# odrb_redraw.net
KiCad netlist of a schematic drawn in EAGLE
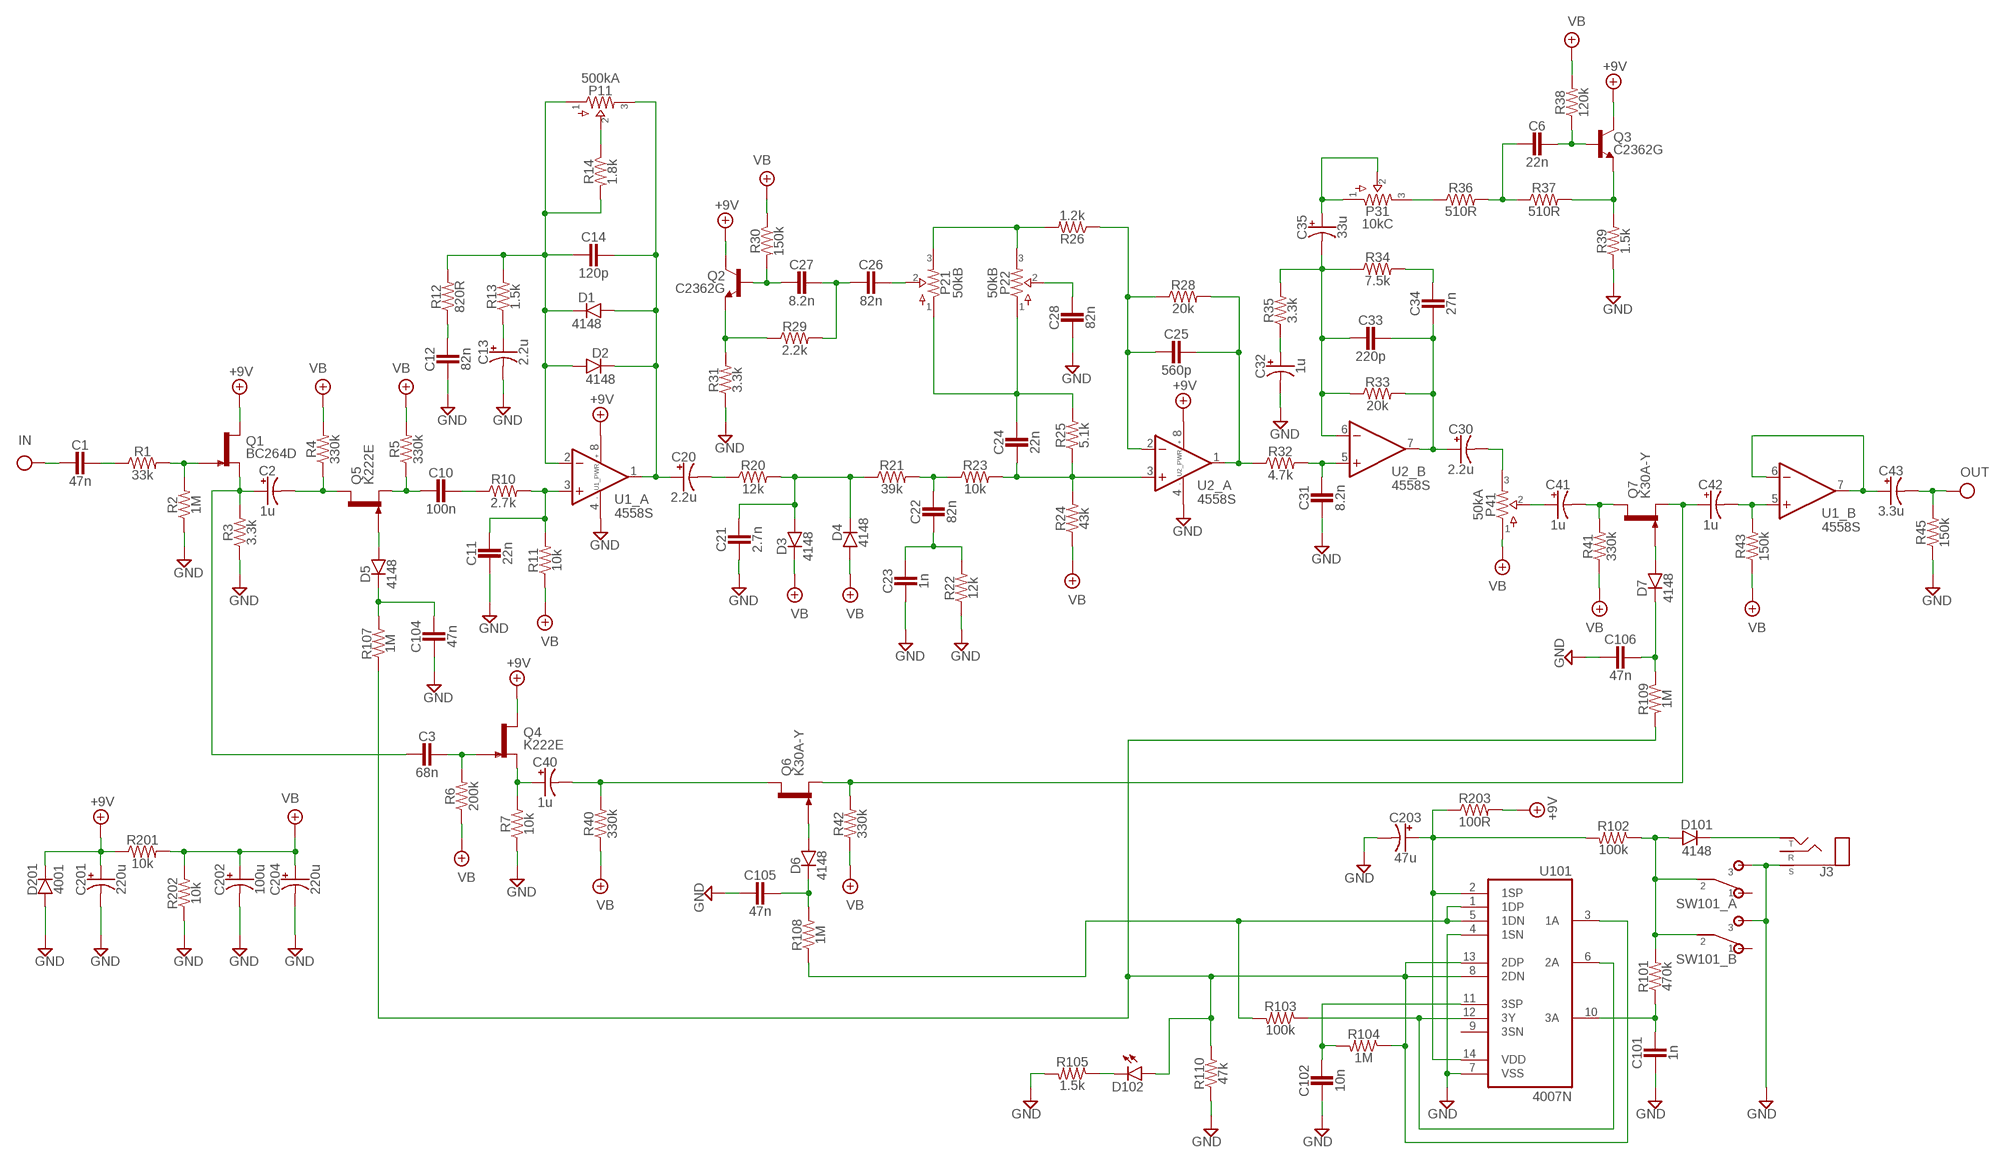
[diagram p0: schematic, sheet 1]

(export (version "E")
  (design (tool "Eeschema 10.0.6"))
  (components
    (comp (ref "C1")
      (value "47n")
      (footprint "eagle-import:BOX_SMALL")
      (libsource (lib "eagle-import") (part "CER/FILMBOX.1"))
    )
    (comp (ref "C2")
      (value "1u")
      (footprint "eagle-import:050_020")
      (libsource (lib "eagle-import") (part "0500"))
    )
    (comp (ref "C3")
      (value "68n")
      (footprint "eagle-import:BOX_SMALL")
      (libsource (lib "eagle-import") (part "CER/FILMBOX.1"))
    )
    (comp (ref "C6")
      (value "22n")
      (footprint "eagle-import:BOX_SMALL")
      (libsource (lib "eagle-import") (part "CER/FILMBOX.1"))
    )
    (comp (ref "C10")
      (value "100n")
      (footprint "eagle-import:BOX_SMALL")
      (libsource (lib "eagle-import") (part "CER/FILMBOX.1"))
    )
    (comp (ref "C11")
      (value "22n")
      (footprint "eagle-import:BOX_SMALL")
      (libsource (lib "eagle-import") (part "CER/FILMBOX.1"))
    )
    (comp (ref "C12")
      (value "82n")
      (footprint "eagle-import:BOX_SMALL")
      (libsource (lib "eagle-import") (part "CER/FILMBOX.1"))
    )
    (comp (ref "C13")
      (value "2.2u")
      (footprint "eagle-import:040_020")
      (libsource (lib "eagle-import") (part "0400"))
    )
    (comp (ref "C14")
      (value "120p")
      (footprint "eagle-import:BOX_SMALL")
      (libsource (lib "eagle-import") (part "CER/FILMBOX.1"))
    )
    (comp (ref "C20")
      (value "2.2u")
      (footprint "eagle-import:040_020")
      (libsource (lib "eagle-import") (part "0400"))
    )
    (comp (ref "C21")
      (value "2.7n")
      (footprint "eagle-import:BOX_SMALL")
      (libsource (lib "eagle-import") (part "CER/FILMBOX.1"))
    )
    (comp (ref "C22")
      (value "82n")
      (footprint "eagle-import:BOX_SMALL")
      (libsource (lib "eagle-import") (part "CER/FILMBOX.1"))
    )
    (comp (ref "C23")
      (value "1n")
      (footprint "eagle-import:BOX_SMALL")
      (libsource (lib "eagle-import") (part "CER/FILMBOX.1"))
    )
    (comp (ref "C24")
      (value "22n")
      (footprint "eagle-import:BOX_SMALL")
      (libsource (lib "eagle-import") (part "CER/FILMBOX.1"))
    )
    (comp (ref "C25")
      (value "560p")
      (footprint "eagle-import:BOX_SMALL")
      (libsource (lib "eagle-import") (part "CER/FILMBOX.1"))
    )
    (comp (ref "C26")
      (value "82n")
      (footprint "eagle-import:BOX_SMALL")
      (libsource (lib "eagle-import") (part "CER/FILMBOX.1"))
    )
    (comp (ref "C27")
      (value "8.2n")
      (footprint "eagle-import:BOX_SMALL")
      (libsource (lib "eagle-import") (part "CER/FILMBOX.1"))
    )
    (comp (ref "C28")
      (value "82n")
      (footprint "eagle-import:BOX_SMALL")
      (libsource (lib "eagle-import") (part "CER/FILMBOX.1"))
    )
    (comp (ref "C30")
      (value "2.2u")
      (footprint "eagle-import:040_020")
      (libsource (lib "eagle-import") (part "0400"))
    )
    (comp (ref "C31")
      (value "8.2n")
      (footprint "eagle-import:BOX_SMALL")
      (libsource (lib "eagle-import") (part "CER/FILMBOX.1"))
    )
    (comp (ref "C32")
      (value "1u")
      (footprint "eagle-import:040_020")
      (libsource (lib "eagle-import") (part "0400"))
    )
    (comp (ref "C33")
      (value "220p")
      (footprint "eagle-import:BOX_SMALL")
      (libsource (lib "eagle-import") (part "CER/FILMBOX.1"))
    )
    (comp (ref "C34")
      (value "27n")
      (footprint "eagle-import:BOX_SMALL")
      (libsource (lib "eagle-import") (part "CER/FILMBOX.1"))
    )
    (comp (ref "C35")
      (value "33u")
      (footprint "eagle-import:040_020")
      (libsource (lib "eagle-import") (part "0400"))
    )
    (comp (ref "C40")
      (value "1u")
      (footprint "eagle-import:040_020")
      (libsource (lib "eagle-import") (part "0400"))
    )
    (comp (ref "C41")
      (value "1u")
      (footprint "eagle-import:040_020")
      (libsource (lib "eagle-import") (part "0400"))
    )
    (comp (ref "C42")
      (value "1u")
      (footprint "eagle-import:040_020")
      (libsource (lib "eagle-import") (part "0400"))
    )
    (comp (ref "C43")
      (value "3.3u")
      (footprint "eagle-import:040_020")
      (libsource (lib "eagle-import") (part "0400"))
    )
    (comp (ref "C101")
      (value "1n")
      (footprint "eagle-import:BOX_SMALL")
      (libsource (lib "eagle-import") (part "CER/FILMBOX.1"))
    )
    (comp (ref "C102")
      (value "10n")
      (footprint "eagle-import:BOX_SMALL")
      (libsource (lib "eagle-import") (part "CER/FILMBOX.1"))
    )
    (comp (ref "C104")
      (value "47n")
      (footprint "eagle-import:BOX_SMALL")
      (libsource (lib "eagle-import") (part "CER/FILMBOX.1"))
    )
    (comp (ref "C105")
      (value "47n")
      (footprint "eagle-import:BOX_SMALL")
      (libsource (lib "eagle-import") (part "CER/FILMBOX.1"))
    )
    (comp (ref "C106")
      (value "47n")
      (footprint "eagle-import:BOX_SMALL")
      (libsource (lib "eagle-import") (part "CER/FILMBOX.1"))
    )
    (comp (ref "C201")
      (value "220u")
      (footprint "eagle-import:040_020")
      (libsource (lib "eagle-import") (part "0400"))
    )
    (comp (ref "C202")
      (value "100u")
      (footprint "eagle-import:040_020")
      (libsource (lib "eagle-import") (part "0400"))
    )
    (comp (ref "C203")
      (value "47u")
      (footprint "eagle-import:040_020")
      (libsource (lib "eagle-import") (part "0400"))
    )
    (comp (ref "C204")
      (value "220u")
      (footprint "eagle-import:040_020")
      (libsource (lib "eagle-import") (part "0400"))
    )
    (comp (ref "D1")
      (value "4148")
      (footprint "eagle-import:DO35-2")
      (libsource (lib "eagle-import") (part "DO35.2"))
    )
    (comp (ref "D2")
      (value "4148")
      (footprint "eagle-import:DO35-2")
      (libsource (lib "eagle-import") (part "DO35.2"))
    )
    (comp (ref "D3")
      (value "4148")
      (footprint "eagle-import:DO35-2")
      (libsource (lib "eagle-import") (part "DO35.2"))
    )
    (comp (ref "D4")
      (value "4148")
      (footprint "eagle-import:DO35-2")
      (libsource (lib "eagle-import") (part "DO35.2"))
    )
    (comp (ref "D5")
      (value "4148")
      (footprint "eagle-import:DO35-2")
      (libsource (lib "eagle-import") (part "DO35.2"))
    )
    (comp (ref "D6")
      (value "4148")
      (footprint "eagle-import:DO35-2")
      (libsource (lib "eagle-import") (part "DO35.2"))
    )
    (comp (ref "D7")
      (value "4148")
      (footprint "eagle-import:DO35-2")
      (libsource (lib "eagle-import") (part "DO35.2"))
    )
    (comp (ref "D101")
      (value "4148")
      (footprint "eagle-import:DO35-2")
      (libsource (lib "eagle-import") (part "DO35.2"))
    )
    (comp (ref "D102")
      (value "LED")
      (footprint "eagle-import:3MM_D")
      (libsource (lib "eagle-import") (part "LED"))
    )
    (comp (ref "D201")
      (value "4001")
      (footprint "eagle-import:DO35-2")
      (libsource (lib "eagle-import") (part "DO35.2"))
    )
    (comp (ref "J3")
      (value "STEREO3PADS")
      (footprint "eagle-import:THREEPADS")
      (libsource (lib "eagle-import") (part "STEREO3PADS"))
    )
    (comp (ref "P11")
      (value "500kA")
      (footprint "eagle-import:16MM")
      (libsource (lib "eagle-import") (part "POTS16MM"))
    )
    (comp (ref "P21")
      (value "50kB")
      (footprint "eagle-import:16MM")
      (libsource (lib "eagle-import") (part "POTS16MM"))
    )
    (comp (ref "P22")
      (value "50kB")
      (footprint "eagle-import:16MM")
      (libsource (lib "eagle-import") (part "POTS16MM"))
    )
    (comp (ref "P31")
      (value "10kC")
      (footprint "eagle-import:16MM")
      (libsource (lib "eagle-import") (part "POTS16MM"))
    )
    (comp (ref "P41")
      (value "50kA")
      (footprint "eagle-import:16MM")
      (libsource (lib "eagle-import") (part "POTS16MM"))
    )
    (comp (ref "Q1")
      (value "BC264D")
      (footprint "eagle-import:TO92-")
      (libsource (lib "eagle-import") (part "2N3819TO-92S"))
    )
    (comp (ref "Q2")
      (value "C2362G")
      (footprint "eagle-import:TO92-")
      (libsource (lib "eagle-import") (part "2N3904"))
    )
    (comp (ref "Q3")
      (value "C2362G")
      (footprint "eagle-import:TO92-")
      (libsource (lib "eagle-import") (part "2N3904"))
    )
    (comp (ref "Q4")
      (value "K222E")
      (footprint "eagle-import:TO92-")
      (libsource (lib "eagle-import") (part "2N3819TO-92S"))
    )
    (comp (ref "Q5")
      (value "K222E")
      (footprint "eagle-import:TO92-")
      (libsource (lib "eagle-import") (part "2N3819TO-92S"))
    )
    (comp (ref "Q6")
      (value "K30A-Y")
      (footprint "eagle-import:TO92-")
      (libsource (lib "eagle-import") (part "2N3819TO-92S"))
    )
    (comp (ref "Q7")
      (value "K30A-Y")
      (footprint "eagle-import:TO92-")
      (libsource (lib "eagle-import") (part "2N3819TO-92S"))
    )
    (comp (ref "R1")
      (value "33k")
      (footprint "eagle-import:R0207_3")
      (libsource (lib "eagle-import") (part "R_.3B"))
    )
    (comp (ref "R2")
      (value "1M")
      (footprint "eagle-import:R0207_3")
      (libsource (lib "eagle-import") (part "R_.3B"))
    )
    (comp (ref "R3")
      (value "3.3k")
      (footprint "eagle-import:R0207_3")
      (libsource (lib "eagle-import") (part "R_.3B"))
    )
    (comp (ref "R4")
      (value "330k")
      (footprint "eagle-import:R0207_3")
      (libsource (lib "eagle-import") (part "R_.3B"))
    )
    (comp (ref "R5")
      (value "330k")
      (footprint "eagle-import:R0207_3")
      (libsource (lib "eagle-import") (part "R_.3B"))
    )
    (comp (ref "R6")
      (value "200k")
      (footprint "eagle-import:R0207_3")
      (libsource (lib "eagle-import") (part "R_.3B"))
    )
    (comp (ref "R7")
      (value "10k")
      (footprint "eagle-import:R0207_3")
      (libsource (lib "eagle-import") (part "R_.3B"))
    )
    (comp (ref "R10")
      (value "2.7k")
      (footprint "eagle-import:R0207_3")
      (libsource (lib "eagle-import") (part "R_.3B"))
    )
    (comp (ref "R11")
      (value "10k")
      (footprint "eagle-import:R0207_3")
      (libsource (lib "eagle-import") (part "R_.3B"))
    )
    (comp (ref "R12")
      (value "820R")
      (footprint "eagle-import:R0207_3")
      (libsource (lib "eagle-import") (part "R_.3B"))
    )
    (comp (ref "R13")
      (value "1.5k")
      (footprint "eagle-import:R0207_3")
      (libsource (lib "eagle-import") (part "R_.3B"))
    )
    (comp (ref "R14")
      (value "1.8k")
      (footprint "eagle-import:R0207_3")
      (libsource (lib "eagle-import") (part "R_.3B"))
    )
    (comp (ref "R20")
      (value "12k")
      (footprint "eagle-import:R0207_3")
      (libsource (lib "eagle-import") (part "R_.3B"))
    )
    (comp (ref "R21")
      (value "39k")
      (footprint "eagle-import:R0207_3")
      (libsource (lib "eagle-import") (part "R_.3B"))
    )
    (comp (ref "R22")
      (value "12k")
      (footprint "eagle-import:R0207_3")
      (libsource (lib "eagle-import") (part "R_.3B"))
    )
    (comp (ref "R23")
      (value "10k")
      (footprint "eagle-import:R0207_3")
      (libsource (lib "eagle-import") (part "R_.3B"))
    )
    (comp (ref "R24")
      (value "43k")
      (footprint "eagle-import:R0207_3")
      (libsource (lib "eagle-import") (part "R_.3B"))
    )
    (comp (ref "R25")
      (value "5.1k")
      (footprint "eagle-import:R0207_3")
      (libsource (lib "eagle-import") (part "R_.3B"))
    )
    (comp (ref "R26")
      (value "1.2k")
      (footprint "eagle-import:R0207_3")
      (libsource (lib "eagle-import") (part "R_.3B"))
    )
    (comp (ref "R28")
      (value "20k")
      (footprint "eagle-import:R0207_3")
      (libsource (lib "eagle-import") (part "R_.3B"))
    )
    (comp (ref "R29")
      (value "2.2k")
      (footprint "eagle-import:R0207_3")
      (libsource (lib "eagle-import") (part "R_.3B"))
    )
    (comp (ref "R30")
      (value "150k")
      (footprint "eagle-import:R0207_3")
      (libsource (lib "eagle-import") (part "R_.3B"))
    )
    (comp (ref "R31")
      (value "3.3k")
      (footprint "eagle-import:R0207_3")
      (libsource (lib "eagle-import") (part "R_.3B"))
    )
    (comp (ref "R32")
      (value "4.7k")
      (footprint "eagle-import:R0207_3")
      (libsource (lib "eagle-import") (part "R_.3B"))
    )
    (comp (ref "R33")
      (value "20k")
      (footprint "eagle-import:R0207_3")
      (libsource (lib "eagle-import") (part "R_.3B"))
    )
    (comp (ref "R34")
      (value "7.5k")
      (footprint "eagle-import:R0207_3")
      (libsource (lib "eagle-import") (part "R_.3B"))
    )
    (comp (ref "R35")
      (value "3.3k")
      (footprint "eagle-import:R0207_3")
      (libsource (lib "eagle-import") (part "R_.3B"))
    )
    (comp (ref "R36")
      (value "510R")
      (footprint "eagle-import:R0207_3")
      (libsource (lib "eagle-import") (part "R_.3B"))
    )
    (comp (ref "R37")
      (value "510R")
      (footprint "eagle-import:R0207_3")
      (libsource (lib "eagle-import") (part "R_.3B"))
    )
    (comp (ref "R38")
      (value "120k")
      (footprint "eagle-import:R0207_3")
      (libsource (lib "eagle-import") (part "R_.3B"))
    )
    (comp (ref "R39")
      (value "1.5k")
      (footprint "eagle-import:R0207_3")
      (libsource (lib "eagle-import") (part "R_.3B"))
    )
    (comp (ref "R40")
      (value "330k")
      (footprint "eagle-import:R0207_3")
      (libsource (lib "eagle-import") (part "R_.3B"))
    )
    (comp (ref "R41")
      (value "330k")
      (footprint "eagle-import:R0207_3")
      (libsource (lib "eagle-import") (part "R_.3B"))
    )
    (comp (ref "R42")
      (value "330k")
      (footprint "eagle-import:R0207_3")
      (libsource (lib "eagle-import") (part "R_.3B"))
    )
    (comp (ref "R43")
      (value "150k")
      (footprint "eagle-import:R0207_3")
      (libsource (lib "eagle-import") (part "R_.3B"))
    )
    (comp (ref "R45")
      (value "150k")
      (footprint "eagle-import:R0207_3")
      (libsource (lib "eagle-import") (part "R_.3B"))
    )
    (comp (ref "R101")
      (value "470k")
      (footprint "eagle-import:R0207_3")
      (libsource (lib "eagle-import") (part "R_.3B"))
    )
    (comp (ref "R102")
      (value "100k")
      (footprint "eagle-import:R0207_3")
      (libsource (lib "eagle-import") (part "R_.3B"))
    )
    (comp (ref "R103")
      (value "100k")
      (footprint "eagle-import:R0207_3")
      (libsource (lib "eagle-import") (part "R_.3B"))
    )
    (comp (ref "R104")
      (value "1M")
      (footprint "eagle-import:R0207_3")
      (libsource (lib "eagle-import") (part "R_.3B"))
    )
    (comp (ref "R105")
      (value "1.5k")
      (footprint "eagle-import:R0207_3")
      (libsource (lib "eagle-import") (part "R_.3B"))
    )
    (comp (ref "R107")
      (value "1M")
      (footprint "eagle-import:R0207_3")
      (libsource (lib "eagle-import") (part "R_.3B"))
    )
    (comp (ref "R108")
      (value "1M")
      (footprint "eagle-import:R0207_3")
      (libsource (lib "eagle-import") (part "R_.3B"))
    )
    (comp (ref "R109")
      (value "1M")
      (footprint "eagle-import:R0207_3")
      (libsource (lib "eagle-import") (part "R_.3B"))
    )
    (comp (ref "R110")
      (value "47k")
      (footprint "eagle-import:R0207_3")
      (libsource (lib "eagle-import") (part "R_.3B"))
    )
    (comp (ref "R201")
      (value "10k")
      (footprint "eagle-import:R0207_3")
      (libsource (lib "eagle-import") (part "R_.3B"))
    )
    (comp (ref "R202")
      (value "10k")
      (footprint "eagle-import:R0207_3")
      (libsource (lib "eagle-import") (part "R_.3B"))
    )
    (comp (ref "R203")
      (value "100R")
      (footprint "eagle-import:R0207_3")
      (libsource (lib "eagle-import") (part "R_.3B"))
    )
    (comp (ref "SW101")
      (value "DPDT")
      (footprint "eagle-import:DPDT")
      (libsource (lib "eagle-import") (part "DPDT"))
    )
    (comp (ref "U1")
      (value "4558S")
      (footprint "eagle-import:DIL0")
      (libsource (lib "eagle-import") (part "DUALTH"))
    )
    (comp (ref "U2")
      (value "4558S")
      (footprint "eagle-import:DIL0")
      (libsource (lib "eagle-import") (part "DUALTH"))
    )
    (comp (ref "U101")
      (value "4007N")
      (footprint "eagle-import:DIL14")
      (libsource (lib "eagle-import") (part "4007N"))
    )
  )
  (nets
    (net (code "1") (name "+9V") (class "Default")
      (node (ref "C201") (pin "+") (pinfunction "+_+") (pintype "passive"))
      (node (ref "D201") (pin "C") (pinfunction "C_C") (pintype "passive"))
      (node (ref "Q1") (pin "3") (pinfunction "D_3") (pintype "passive"))
      (node (ref "Q2") (pin "1") (pinfunction "C_1") (pintype "passive"))
      (node (ref "Q3") (pin "1") (pinfunction "C_1") (pintype "passive"))
      (node (ref "Q4") (pin "3") (pinfunction "D_3") (pintype "passive"))
      (node (ref "R201") (pin "1") (pinfunction "1_1") (pintype "passive"))
      (node (ref "R203") (pin "2") (pinfunction "2_2") (pintype "passive"))
      (node (ref "U1") (pin "8") (pinfunction "V+_8") (pintype "power_in"))
      (node (ref "U2") (pin "8") (pinfunction "V+_8") (pintype "power_in"))
    )
    (net (code "2") (name "GND") (class "Default")
      (node (ref "C101") (pin "2") (pinfunction "2_2") (pintype "passive"))
      (node (ref "C102") (pin "2") (pinfunction "2_2") (pintype "passive"))
      (node (ref "C104") (pin "1") (pinfunction "1_1") (pintype "passive"))
      (node (ref "C105") (pin "2") (pinfunction "2_2") (pintype "passive"))
      (node (ref "C106") (pin "2") (pinfunction "2_2") (pintype "passive"))
      (node (ref "C11") (pin "2") (pinfunction "2_2") (pintype "passive"))
      (node (ref "C12") (pin "2") (pinfunction "2_2") (pintype "passive"))
      (node (ref "C13") (pin "-") (pinfunction "-_-") (pintype "passive"))
      (node (ref "C201") (pin "-") (pinfunction "-_-") (pintype "passive"))
      (node (ref "C202") (pin "-") (pinfunction "-_-") (pintype "passive"))
      (node (ref "C203") (pin "-") (pinfunction "-_-") (pintype "passive"))
      (node (ref "C204") (pin "-") (pinfunction "-_-") (pintype "passive"))
      (node (ref "C21") (pin "2") (pinfunction "2_2") (pintype "passive"))
      (node (ref "C23") (pin "2") (pinfunction "2_2") (pintype "passive"))
      (node (ref "C28") (pin "2") (pinfunction "2_2") (pintype "passive"))
      (node (ref "C31") (pin "2") (pinfunction "2_2") (pintype "passive"))
      (node (ref "C32") (pin "-") (pinfunction "-_-") (pintype "passive"))
      (node (ref "D201") (pin "A") (pinfunction "A_A") (pintype "passive"))
      (node (ref "J3") (pin "SLEEVE") (pinfunction "S_SLEEVE") (pintype "passive"))
      (node (ref "R105") (pin "2") (pinfunction "2_2") (pintype "passive"))
      (node (ref "R110") (pin "1") (pinfunction "1_1") (pintype "passive"))
      (node (ref "R2") (pin "1") (pinfunction "1_1") (pintype "passive"))
      (node (ref "R202") (pin "1") (pinfunction "1_1") (pintype "passive"))
      (node (ref "R22") (pin "1") (pinfunction "1_1") (pintype "passive"))
      (node (ref "R3") (pin "1") (pinfunction "1_1") (pintype "passive"))
      (node (ref "R31") (pin "1") (pinfunction "1_1") (pintype "passive"))
      (node (ref "R39") (pin "1") (pinfunction "1_1") (pintype "passive"))
      (node (ref "R45") (pin "1") (pinfunction "1_1") (pintype "passive"))
      (node (ref "R7") (pin "1") (pinfunction "1_1") (pintype "passive"))
      (node (ref "SW101") (pin "A3") (pinfunction "3_A3") (pintype "passive"))
      (node (ref "SW101") (pin "B3") (pinfunction "3_B3") (pintype "passive"))
      (node (ref "U1") (pin "4") (pinfunction "V-_4") (pintype "power_in"))
      (node (ref "U101") (pin "4") (pinfunction "1SN_4") (pintype "open_collector"))
      (node (ref "U101") (pin "7") (pinfunction "VSS_7") (pintype "input"))
      (node (ref "U2") (pin "4") (pinfunction "V-_4") (pintype "power_in"))
    )
    (net (code "3") (name "IN") (class "Default")
      (node (ref "C1") (pin "2") (pinfunction "2_2") (pintype "passive"))
    )
    (net (code "4") (name "Net-(C1-Pad1)") (class "Default")
      (node (ref "C1") (pin "1") (pinfunction "1_1") (pintype "passive"))
      (node (ref "R1") (pin "1") (pinfunction "1_1") (pintype "passive"))
    )
    (net (code "5") (name "Net-(C6-Pad2)") (class "Default")
      (node (ref "C6") (pin "2") (pinfunction "2_2") (pintype "passive"))
      (node (ref "R36") (pin "2") (pinfunction "2_2") (pintype "passive"))
      (node (ref "R37") (pin "1") (pinfunction "1_1") (pintype "passive"))
    )
    (net (code "6") (name "Net-(C10-Pad1)") (class "Default")
      (node (ref "C10") (pin "1") (pinfunction "1_1") (pintype "passive"))
      (node (ref "R10") (pin "1") (pinfunction "1_1") (pintype "passive"))
    )
    (net (code "7") (name "Net-(C12-Pad1)") (class "Default")
      (node (ref "C12") (pin "1") (pinfunction "1_1") (pintype "passive"))
      (node (ref "R12") (pin "1") (pinfunction "1_1") (pintype "passive"))
    )
    (net (code "8") (name "Net-(C13-Pad+)") (class "Default")
      (node (ref "C13") (pin "+") (pinfunction "+_+") (pintype "passive"))
      (node (ref "R13") (pin "1") (pinfunction "1_1") (pintype "passive"))
    )
    (net (code "9") (name "Net-(C20-Pad-)") (class "Default")
      (node (ref "C20") (pin "-") (pinfunction "-_-") (pintype "passive"))
      (node (ref "R20") (pin "1") (pinfunction "1_1") (pintype "passive"))
    )
    (net (code "10") (name "Net-(C21-Pad1)") (class "Default")
      (node (ref "C21") (pin "1") (pinfunction "1_1") (pintype "passive"))
      (node (ref "D3") (pin "A") (pinfunction "A_A") (pintype "passive"))
      (node (ref "D4") (pin "C") (pinfunction "C_C") (pintype "passive"))
      (node (ref "R20") (pin "2") (pinfunction "2_2") (pintype "passive"))
      (node (ref "R21") (pin "1") (pinfunction "1_1") (pintype "passive"))
    )
    (net (code "11") (name "Net-(C22-Pad1)") (class "Default")
      (node (ref "C22") (pin "1") (pinfunction "1_1") (pintype "passive"))
      (node (ref "R21") (pin "2") (pinfunction "2_2") (pintype "passive"))
      (node (ref "R23") (pin "1") (pinfunction "1_1") (pintype "passive"))
    )
    (net (code "12") (name "Net-(C22-Pad2)") (class "Default")
      (node (ref "C22") (pin "2") (pinfunction "2_2") (pintype "passive"))
      (node (ref "C23") (pin "1") (pinfunction "1_1") (pintype "passive"))
      (node (ref "R22") (pin "2") (pinfunction "2_2") (pintype "passive"))
    )
    (net (code "13") (name "Net-(C24-Pad1)") (class "Default")
      (node (ref "C24") (pin "1") (pinfunction "1_1") (pintype "passive"))
      (node (ref "P21") (pin "1") (pinfunction "1_1") (pintype "passive"))
      (node (ref "P22") (pin "1") (pinfunction "1_1") (pintype "passive"))
      (node (ref "R25") (pin "2") (pinfunction "2_2") (pintype "passive"))
    )
    (net (code "14") (name "Net-(C26-Pad1)") (class "Default")
      (node (ref "C26") (pin "1") (pinfunction "1_1") (pintype "passive"))
      (node (ref "P21") (pin "2") (pinfunction "2_2") (pintype "passive"))
    )
    (net (code "15") (name "Net-(C26-Pad2)") (class "Default")
      (node (ref "C26") (pin "2") (pinfunction "2_2") (pintype "passive"))
      (node (ref "C27") (pin "1") (pinfunction "1_1") (pintype "passive"))
      (node (ref "R29") (pin "2") (pinfunction "2_2") (pintype "passive"))
    )
    (net (code "16") (name "Net-(C28-Pad1)") (class "Default")
      (node (ref "C28") (pin "1") (pinfunction "1_1") (pintype "passive"))
      (node (ref "P22") (pin "2") (pinfunction "2_2") (pintype "passive"))
    )
    (net (code "17") (name "Net-(C30-Pad-)") (class "Default")
      (node (ref "C30") (pin "-") (pinfunction "-_-") (pintype "passive"))
      (node (ref "P41") (pin "3") (pinfunction "3_3") (pintype "passive"))
    )
    (net (code "18") (name "Net-(C32-Pad+)") (class "Default")
      (node (ref "C32") (pin "+") (pinfunction "+_+") (pintype "passive"))
      (node (ref "R35") (pin "1") (pinfunction "1_1") (pintype "passive"))
    )
    (net (code "19") (name "Net-(C34-Pad1)") (class "Default")
      (node (ref "C34") (pin "1") (pinfunction "1_1") (pintype "passive"))
      (node (ref "R34") (pin "2") (pinfunction "2_2") (pintype "passive"))
    )
    (net (code "20") (name "Net-(C35-Pad+)") (class "Default")
      (node (ref "C35") (pin "+") (pinfunction "+_+") (pintype "passive"))
      (node (ref "P31") (pin "1") (pinfunction "1_1") (pintype "passive"))
      (node (ref "P31") (pin "2") (pinfunction "2_2") (pintype "passive"))
    )
    (net (code "21") (name "Net-(C41-Pad+)") (class "Default")
      (node (ref "C41") (pin "+") (pinfunction "+_+") (pintype "passive"))
      (node (ref "P41") (pin "2") (pinfunction "2_2") (pintype "passive"))
    )
    (net (code "22") (name "Net-(C104-Pad2)") (class "Default")
      (node (ref "C104") (pin "2") (pinfunction "2_2") (pintype "passive"))
      (node (ref "D5") (pin "C") (pinfunction "C_C") (pintype "passive"))
      (node (ref "R107") (pin "2") (pinfunction "2_2") (pintype "passive"))
    )
    (net (code "23") (name "Net-(C105-Pad1)") (class "Default")
      (node (ref "C105") (pin "1") (pinfunction "1_1") (pintype "passive"))
      (node (ref "D6") (pin "C") (pinfunction "C_C") (pintype "passive"))
      (node (ref "R108") (pin "2") (pinfunction "2_2") (pintype "passive"))
    )
    (net (code "24") (name "Net-(C106-Pad1)") (class "Default")
      (node (ref "C106") (pin "1") (pinfunction "1_1") (pintype "passive"))
      (node (ref "D7") (pin "C") (pinfunction "C_C") (pintype "passive"))
      (node (ref "R109") (pin "1") (pinfunction "1_1") (pintype "passive"))
    )
    (net (code "25") (name "Net-(D102-A)") (class "Default")
      (node (ref "D102") (pin "ANODE") (pinfunction "A_ANODE") (pintype "passive"))
      (node (ref "R104") (pin "1") (pinfunction "1_1") (pintype "passive"))
      (node (ref "R107") (pin "1") (pinfunction "1_1") (pintype "passive"))
      (node (ref "R109") (pin "2") (pinfunction "2_2") (pintype "passive"))
      (node (ref "R110") (pin "2") (pinfunction "2_2") (pintype "passive"))
      (node (ref "U101") (pin "13") (pinfunction "2DP_13") (pintype "bidirectional"))
      (node (ref "U101") (pin "3") (pinfunction "1A_3") (pintype "input"))
      (node (ref "U101") (pin "8") (pinfunction "2DN_8") (pintype "bidirectional"))
    )
    (net (code "26") (name "Net-(D102-C)") (class "Default")
      (node (ref "D102") (pin "P$1") (pinfunction "C_P$1") (pintype "passive"))
      (node (ref "R105") (pin "1") (pinfunction "1_1") (pintype "passive"))
    )
    (net (code "27") (name "Net-(J3-T)") (class "Default")
      (node (ref "D101") (pin "C") (pinfunction "C_C") (pintype "passive"))
      (node (ref "J3") (pin "TIP") (pinfunction "T_TIP") (pintype "passive"))
    )
    (net (code "28") (name "Net-(P11-Pad2)") (class "Default")
      (node (ref "P11") (pin "2") (pinfunction "2_2") (pintype "passive"))
      (node (ref "R14") (pin "1") (pinfunction "1_1") (pintype "passive"))
    )
    (net (code "29") (name "Net-(P21-Pad3)") (class "Default")
      (node (ref "P21") (pin "3") (pinfunction "3_3") (pintype "passive"))
      (node (ref "P22") (pin "3") (pinfunction "3_3") (pintype "passive"))
      (node (ref "R26") (pin "2") (pinfunction "2_2") (pintype "passive"))
    )
    (net (code "30") (name "Net-(P31-Pad3)") (class "Default")
      (node (ref "P31") (pin "3") (pinfunction "3_3") (pintype "passive"))
      (node (ref "R36") (pin "1") (pinfunction "1_1") (pintype "passive"))
    )
    (net (code "31") (name "Net-(Q1-G)") (class "Default")
      (node (ref "Q1") (pin "2") (pinfunction "G_2") (pintype "passive"))
      (node (ref "R1") (pin "2") (pinfunction "2_2") (pintype "passive"))
      (node (ref "R2") (pin "2") (pinfunction "2_2") (pintype "passive"))
    )
    (net (code "32") (name "Net-(Q1-S)") (class "Default")
      (node (ref "C2") (pin "+") (pinfunction "+_+") (pintype "passive"))
      (node (ref "C3") (pin "2") (pinfunction "2_2") (pintype "passive"))
      (node (ref "Q1") (pin "1") (pinfunction "S_1") (pintype "passive"))
      (node (ref "R3") (pin "2") (pinfunction "2_2") (pintype "passive"))
    )
    (net (code "33") (name "Net-(Q2-B)") (class "Default")
      (node (ref "C27") (pin "2") (pinfunction "2_2") (pintype "passive"))
      (node (ref "Q2") (pin "2") (pinfunction "B_2") (pintype "passive"))
      (node (ref "R30") (pin "2") (pinfunction "2_2") (pintype "passive"))
    )
    (net (code "34") (name "Net-(Q2-E)") (class "Default")
      (node (ref "Q2") (pin "3") (pinfunction "E_3") (pintype "passive"))
      (node (ref "R29") (pin "1") (pinfunction "1_1") (pintype "passive"))
      (node (ref "R31") (pin "2") (pinfunction "2_2") (pintype "passive"))
    )
    (net (code "35") (name "Net-(Q3-B)") (class "Default")
      (node (ref "C6") (pin "1") (pinfunction "1_1") (pintype "passive"))
      (node (ref "Q3") (pin "2") (pinfunction "B_2") (pintype "passive"))
      (node (ref "R38") (pin "1") (pinfunction "1_1") (pintype "passive"))
    )
    (net (code "36") (name "Net-(Q3-E)") (class "Default")
      (node (ref "Q3") (pin "3") (pinfunction "E_3") (pintype "passive"))
      (node (ref "R37") (pin "2") (pinfunction "2_2") (pintype "passive"))
      (node (ref "R39") (pin "2") (pinfunction "2_2") (pintype "passive"))
    )
    (net (code "37") (name "Net-(Q4-G)") (class "Default")
      (node (ref "C3") (pin "1") (pinfunction "1_1") (pintype "passive"))
      (node (ref "Q4") (pin "2") (pinfunction "G_2") (pintype "passive"))
      (node (ref "R6") (pin "2") (pinfunction "2_2") (pintype "passive"))
    )
    (net (code "38") (name "Net-(Q4-S)") (class "Default")
      (node (ref "C40") (pin "+") (pinfunction "+_+") (pintype "passive"))
      (node (ref "Q4") (pin "1") (pinfunction "S_1") (pintype "passive"))
      (node (ref "R7") (pin "2") (pinfunction "2_2") (pintype "passive"))
    )
    (net (code "39") (name "Net-(Q5-D)") (class "Default")
      (node (ref "C2") (pin "-") (pinfunction "-_-") (pintype "passive"))
      (node (ref "Q5") (pin "3") (pinfunction "D_3") (pintype "passive"))
      (node (ref "R4") (pin "1") (pinfunction "1_1") (pintype "passive"))
    )
    (net (code "40") (name "Net-(Q5-G)") (class "Default")
      (node (ref "D5") (pin "A") (pinfunction "A_A") (pintype "passive"))
      (node (ref "Q5") (pin "2") (pinfunction "G_2") (pintype "passive"))
    )
    (net (code "41") (name "Net-(Q5-S)") (class "Default")
      (node (ref "C10") (pin "2") (pinfunction "2_2") (pintype "passive"))
      (node (ref "Q5") (pin "1") (pinfunction "S_1") (pintype "passive"))
      (node (ref "R5") (pin "1") (pinfunction "1_1") (pintype "passive"))
    )
    (net (code "42") (name "Net-(Q6-D)") (class "Default")
      (node (ref "C40") (pin "-") (pinfunction "-_-") (pintype "passive"))
      (node (ref "Q6") (pin "3") (pinfunction "D_3") (pintype "passive"))
      (node (ref "R40") (pin "2") (pinfunction "2_2") (pintype "passive"))
    )
    (net (code "43") (name "Net-(Q6-G)") (class "Default")
      (node (ref "D6") (pin "A") (pinfunction "A_A") (pintype "passive"))
      (node (ref "Q6") (pin "2") (pinfunction "G_2") (pintype "passive"))
    )
    (net (code "44") (name "Net-(Q6-S)") (class "Default")
      (node (ref "C42") (pin "+") (pinfunction "+_+") (pintype "passive"))
      (node (ref "Q6") (pin "1") (pinfunction "S_1") (pintype "passive"))
      (node (ref "Q7") (pin "1") (pinfunction "S_1") (pintype "passive"))
      (node (ref "R42") (pin "2") (pinfunction "2_2") (pintype "passive"))
    )
    (net (code "45") (name "Net-(Q7-D)") (class "Default")
      (node (ref "C41") (pin "-") (pinfunction "-_-") (pintype "passive"))
      (node (ref "Q7") (pin "3") (pinfunction "D_3") (pintype "passive"))
      (node (ref "R41") (pin "2") (pinfunction "2_2") (pintype "passive"))
    )
    (net (code "46") (name "Net-(Q7-G)") (class "Default")
      (node (ref "D7") (pin "A") (pinfunction "A_A") (pintype "passive"))
      (node (ref "Q7") (pin "2") (pinfunction "G_2") (pintype "passive"))
    )
    (net (code "47") (name "Net-(SW101A-2)") (class "Default")
      (node (ref "D101") (pin "A") (pinfunction "A_A") (pintype "passive"))
      (node (ref "R101") (pin "2") (pinfunction "2_2") (pintype "passive"))
      (node (ref "R102") (pin "1") (pinfunction "1_1") (pintype "passive"))
      (node (ref "SW101") (pin "A2") (pinfunction "2_A2") (pintype "passive"))
      (node (ref "SW101") (pin "B2") (pinfunction "2_B2") (pintype "passive"))
    )
    (net (code "48") (name "Net-(U1A-+IN)") (class "Default")
      (node (ref "C11") (pin "1") (pinfunction "1_1") (pintype "passive"))
      (node (ref "R10") (pin "2") (pinfunction "2_2") (pintype "passive"))
      (node (ref "R11") (pin "2") (pinfunction "2_2") (pintype "passive"))
      (node (ref "U1") (pin "3") (pinfunction "+IN_3") (pintype "input"))
    )
    (net (code "49") (name "Net-(U1A--IN)") (class "Default")
      (node (ref "C14") (pin "2") (pinfunction "2_2") (pintype "passive"))
      (node (ref "D1") (pin "C") (pinfunction "C_C") (pintype "passive"))
      (node (ref "D2") (pin "A") (pinfunction "A_A") (pintype "passive"))
      (node (ref "P11") (pin "1") (pinfunction "1_1") (pintype "passive"))
      (node (ref "R12") (pin "2") (pinfunction "2_2") (pintype "passive"))
      (node (ref "R13") (pin "2") (pinfunction "2_2") (pintype "passive"))
      (node (ref "R14") (pin "2") (pinfunction "2_2") (pintype "passive"))
      (node (ref "U1") (pin "2") (pinfunction "-IN_2") (pintype "input"))
    )
    (net (code "50") (name "Net-(U1A-OUT)") (class "Default")
      (node (ref "C14") (pin "1") (pinfunction "1_1") (pintype "passive"))
      (node (ref "C20") (pin "+") (pinfunction "+_+") (pintype "passive"))
      (node (ref "D1") (pin "A") (pinfunction "A_A") (pintype "passive"))
      (node (ref "D2") (pin "C") (pinfunction "C_C") (pintype "passive"))
      (node (ref "P11") (pin "3") (pinfunction "3_3") (pintype "passive"))
      (node (ref "U1") (pin "1") (pinfunction "OUT_1") (pintype "output"))
    )
    (net (code "51") (name "Net-(U1B-+IN)") (class "Default")
      (node (ref "C42") (pin "-") (pinfunction "-_-") (pintype "passive"))
      (node (ref "R43") (pin "2") (pinfunction "2_2") (pintype "passive"))
      (node (ref "U1") (pin "5") (pinfunction "+IN_5") (pintype "input"))
    )
    (net (code "52") (name "Net-(U1B--IN)") (class "Default")
      (node (ref "C43") (pin "+") (pinfunction "+_+") (pintype "passive"))
      (node (ref "U1") (pin "6") (pinfunction "-IN_6") (pintype "input"))
      (node (ref "U1") (pin "7") (pinfunction "OUT_7") (pintype "output"))
    )
    (net (code "53") (name "Net-(U2A-+IN)") (class "Default")
      (node (ref "C24") (pin "2") (pinfunction "2_2") (pintype "passive"))
      (node (ref "R23") (pin "2") (pinfunction "2_2") (pintype "passive"))
      (node (ref "R24") (pin "2") (pinfunction "2_2") (pintype "passive"))
      (node (ref "R25") (pin "1") (pinfunction "1_1") (pintype "passive"))
      (node (ref "U2") (pin "3") (pinfunction "+IN_3") (pintype "input"))
    )
    (net (code "54") (name "Net-(U2A--IN)") (class "Default")
      (node (ref "C25") (pin "2") (pinfunction "2_2") (pintype "passive"))
      (node (ref "R26") (pin "1") (pinfunction "1_1") (pintype "passive"))
      (node (ref "R28") (pin "1") (pinfunction "1_1") (pintype "passive"))
      (node (ref "U2") (pin "2") (pinfunction "-IN_2") (pintype "input"))
    )
    (net (code "55") (name "Net-(U2A-OUT)") (class "Default")
      (node (ref "C25") (pin "1") (pinfunction "1_1") (pintype "passive"))
      (node (ref "R28") (pin "2") (pinfunction "2_2") (pintype "passive"))
      (node (ref "R32") (pin "1") (pinfunction "1_1") (pintype "passive"))
      (node (ref "U2") (pin "1") (pinfunction "OUT_1") (pintype "output"))
    )
    (net (code "56") (name "Net-(U2B-+IN)") (class "Default")
      (node (ref "C31") (pin "1") (pinfunction "1_1") (pintype "passive"))
      (node (ref "R32") (pin "2") (pinfunction "2_2") (pintype "passive"))
      (node (ref "U2") (pin "5") (pinfunction "+IN_5") (pintype "input"))
    )
    (net (code "57") (name "Net-(U2B--IN)") (class "Default")
      (node (ref "C33") (pin "2") (pinfunction "2_2") (pintype "passive"))
      (node (ref "C35") (pin "-") (pinfunction "-_-") (pintype "passive"))
      (node (ref "R33") (pin "1") (pinfunction "1_1") (pintype "passive"))
      (node (ref "R34") (pin "1") (pinfunction "1_1") (pintype "passive"))
      (node (ref "R35") (pin "2") (pinfunction "2_2") (pintype "passive"))
      (node (ref "U2") (pin "6") (pinfunction "-IN_6") (pintype "input"))
    )
    (net (code "58") (name "Net-(U2B-OUT)") (class "Default")
      (node (ref "C30") (pin "+") (pinfunction "+_+") (pintype "passive"))
      (node (ref "C33") (pin "1") (pinfunction "1_1") (pintype "passive"))
      (node (ref "C34") (pin "2") (pinfunction "2_2") (pintype "passive"))
      (node (ref "R33") (pin "2") (pinfunction "2_2") (pintype "passive"))
      (node (ref "U2") (pin "7") (pinfunction "OUT_7") (pintype "output"))
    )
    (net (code "59") (name "Net-(U101-1DN)") (class "Default")
      (node (ref "R103") (pin "2") (pinfunction "2_2") (pintype "passive"))
      (node (ref "R108") (pin "1") (pinfunction "1_1") (pintype "passive"))
      (node (ref "U101") (pin "1") (pinfunction "1DP_1") (pintype "open_collector"))
      (node (ref "U101") (pin "5") (pinfunction "1DN_5") (pintype "open_collector"))
    )
    (net (code "60") (name "Net-(U101-1SP)") (class "Default")
      (node (ref "C203") (pin "+") (pinfunction "+_+") (pintype "passive"))
      (node (ref "R102") (pin "2") (pinfunction "2_2") (pintype "passive"))
      (node (ref "R203") (pin "1") (pinfunction "1_1") (pintype "passive"))
      (node (ref "U101") (pin "14") (pinfunction "VDD_14") (pintype "input"))
      (node (ref "U101") (pin "2") (pinfunction "1SP_2") (pintype "open_collector"))
    )
    (net (code "61") (name "Net-(U101-2A)") (class "Default")
      (node (ref "R103") (pin "1") (pinfunction "1_1") (pintype "passive"))
      (node (ref "U101") (pin "12") (pinfunction "3Y_12") (pintype "bidirectional"))
      (node (ref "U101") (pin "6") (pinfunction "2A_6") (pintype "input"))
    )
    (net (code "62") (name "Net-(U101-3A)") (class "Default")
      (node (ref "C101") (pin "1") (pinfunction "1_1") (pintype "passive"))
      (node (ref "R101") (pin "1") (pinfunction "1_1") (pintype "passive"))
      (node (ref "U101") (pin "10") (pinfunction "3A_10") (pintype "input"))
    )
    (net (code "63") (name "Net-(U101-3SP)") (class "Default")
      (node (ref "C102") (pin "1") (pinfunction "1_1") (pintype "passive"))
      (node (ref "R104") (pin "2") (pinfunction "2_2") (pintype "passive"))
      (node (ref "U101") (pin "11") (pinfunction "3SP_11") (pintype "bidirectional"))
    )
    (net (code "64") (name "OUT") (class "Default")
      (node (ref "C43") (pin "-") (pinfunction "-_-") (pintype "passive"))
      (node (ref "R45") (pin "2") (pinfunction "2_2") (pintype "passive"))
    )
    (net (code "65") (name "VB") (class "Default")
      (node (ref "C202") (pin "+") (pinfunction "+_+") (pintype "passive"))
      (node (ref "C204") (pin "+") (pinfunction "+_+") (pintype "passive"))
      (node (ref "D3") (pin "C") (pinfunction "C_C") (pintype "passive"))
      (node (ref "D4") (pin "A") (pinfunction "A_A") (pintype "passive"))
      (node (ref "P41") (pin "1") (pinfunction "1_1") (pintype "passive"))
      (node (ref "R11") (pin "1") (pinfunction "1_1") (pintype "passive"))
      (node (ref "R201") (pin "2") (pinfunction "2_2") (pintype "passive"))
      (node (ref "R202") (pin "2") (pinfunction "2_2") (pintype "passive"))
      (node (ref "R24") (pin "1") (pinfunction "1_1") (pintype "passive"))
      (node (ref "R30") (pin "1") (pinfunction "1_1") (pintype "passive"))
      (node (ref "R38") (pin "2") (pinfunction "2_2") (pintype "passive"))
      (node (ref "R4") (pin "2") (pinfunction "2_2") (pintype "passive"))
      (node (ref "R40") (pin "1") (pinfunction "1_1") (pintype "passive"))
      (node (ref "R41") (pin "1") (pinfunction "1_1") (pintype "passive"))
      (node (ref "R42") (pin "1") (pinfunction "1_1") (pintype "passive"))
      (node (ref "R43") (pin "1") (pinfunction "1_1") (pintype "passive"))
      (node (ref "R5") (pin "2") (pinfunction "2_2") (pintype "passive"))
      (node (ref "R6") (pin "1") (pinfunction "1_1") (pintype "passive"))
    )
    (net (code "66") (name "unconnected-(J3-R-PadRING)") (class "Default")
      (node (ref "J3") (pin "RING") (pinfunction "R_RING") (pintype "passive"))
    )
    (net (code "67") (name "unconnected-(SW101A-1-PadA1)") (class "Default")
      (node (ref "SW101") (pin "A1") (pinfunction "1_A1") (pintype "passive"))
    )
    (net (code "68") (name "unconnected-(SW101B-1-PadB1)") (class "Default")
      (node (ref "SW101") (pin "B1") (pinfunction "1_B1") (pintype "passive"))
    )
    (net (code "69") (name "unconnected-(U101-3SN-Pad9)") (class "Default")
      (node (ref "U101") (pin "9") (pinfunction "3SN_9") (pintype "bidirectional"))
    )
  )
)
